# LGT-92_v1_5.net
KiCad netlist of a schematic drawn in EAGLE
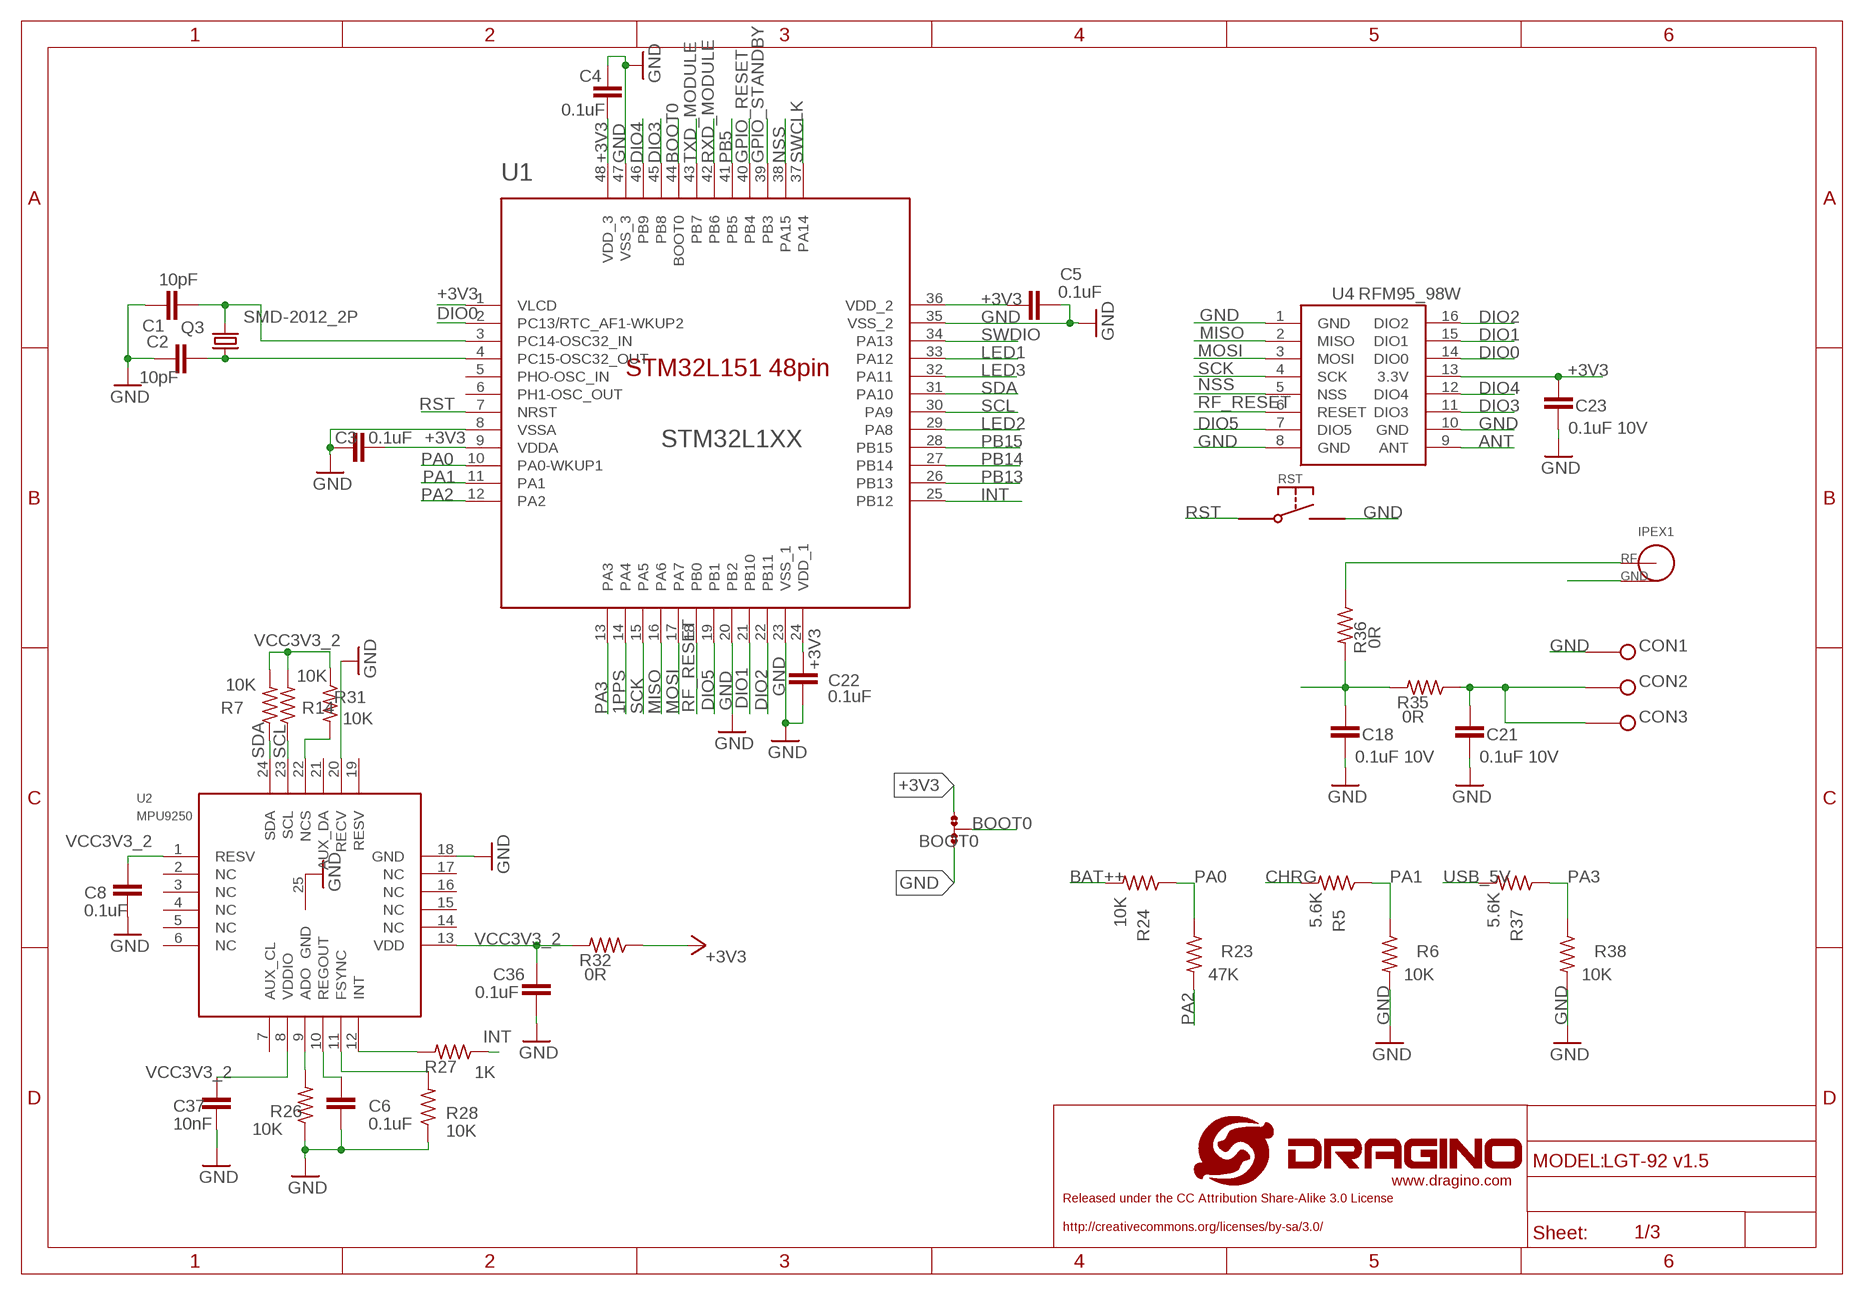
[diagram p0: schematic, sheet 1]
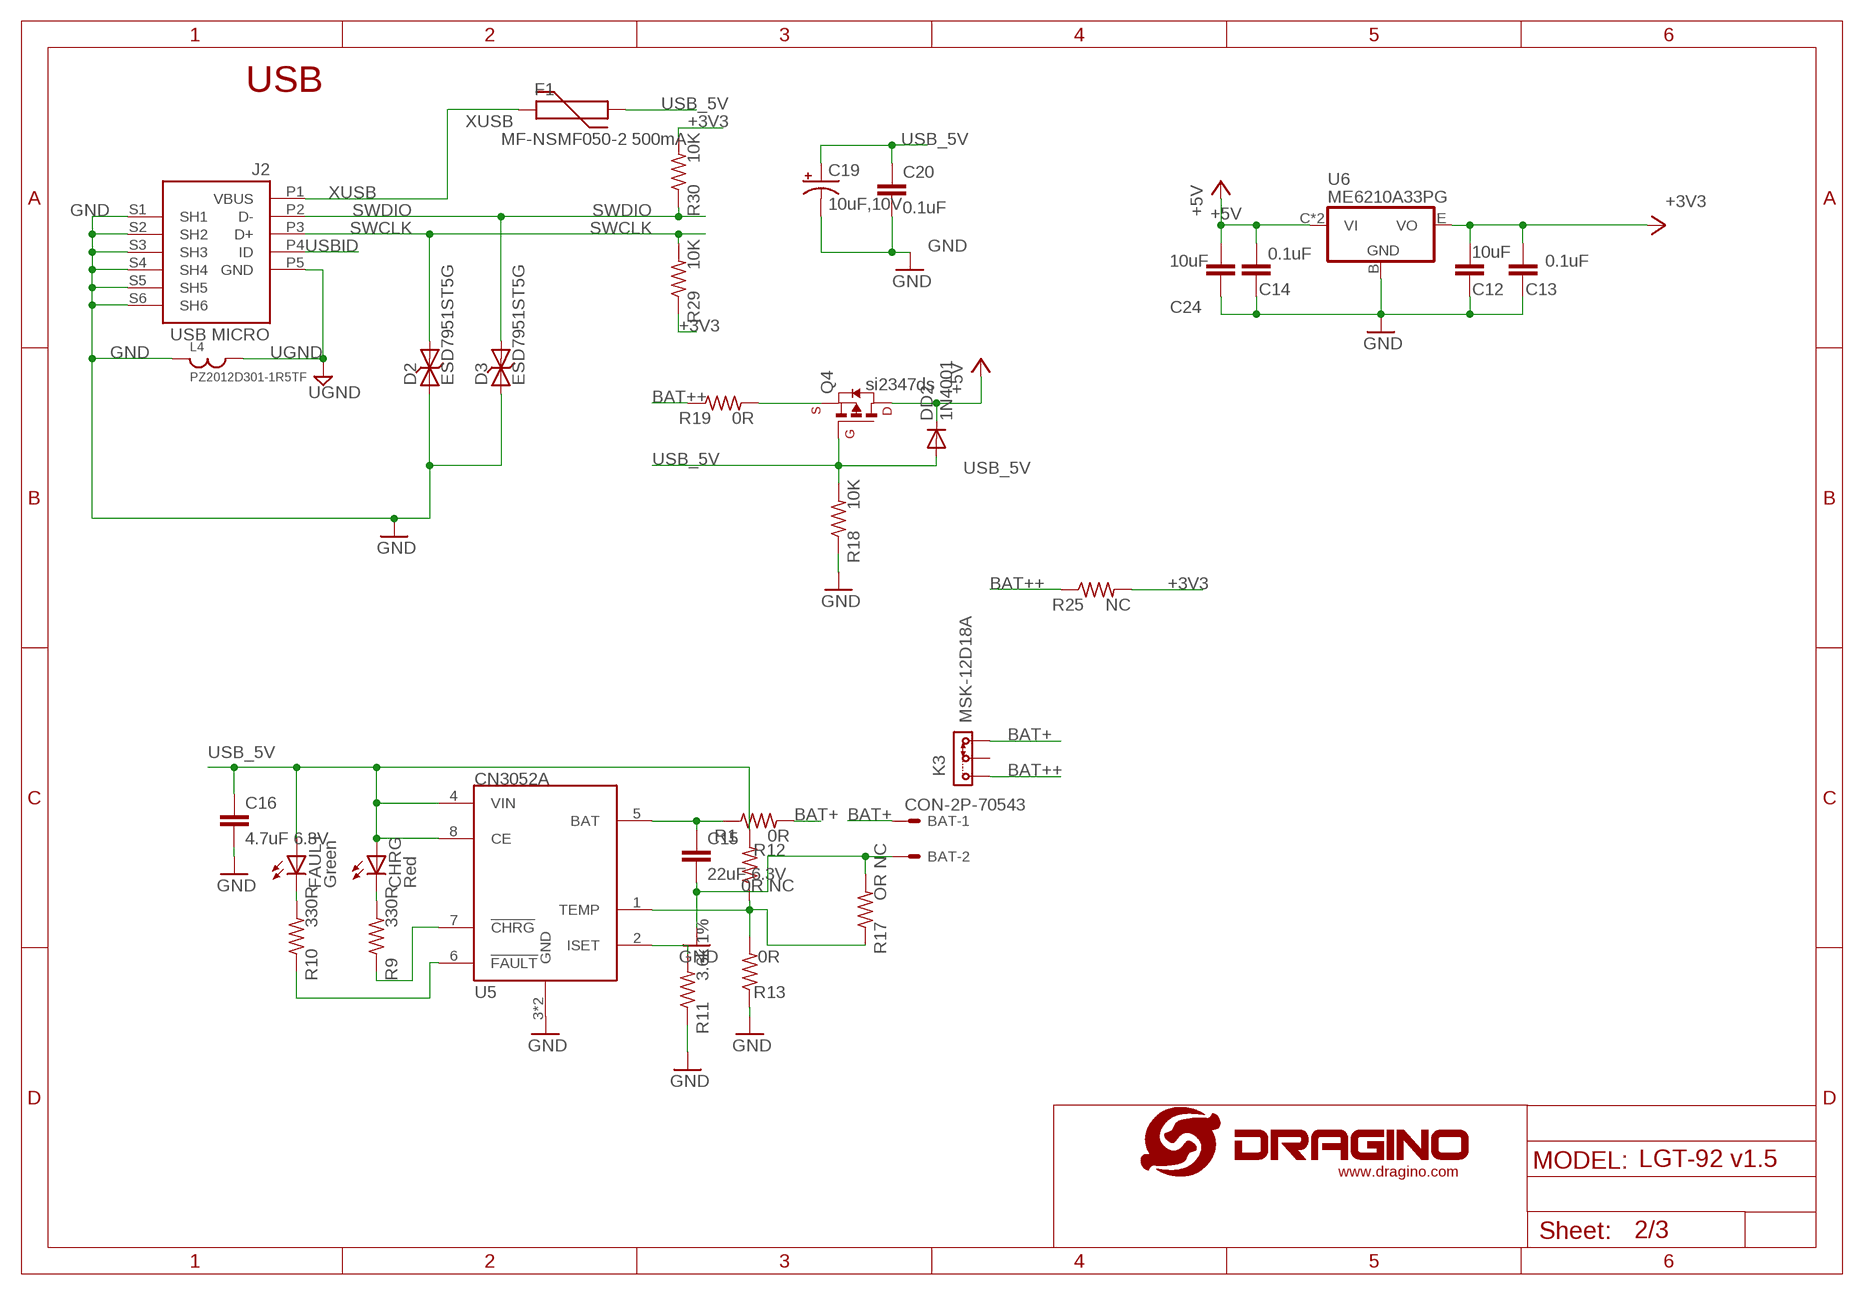
[diagram p1: schematic, sheet 2]
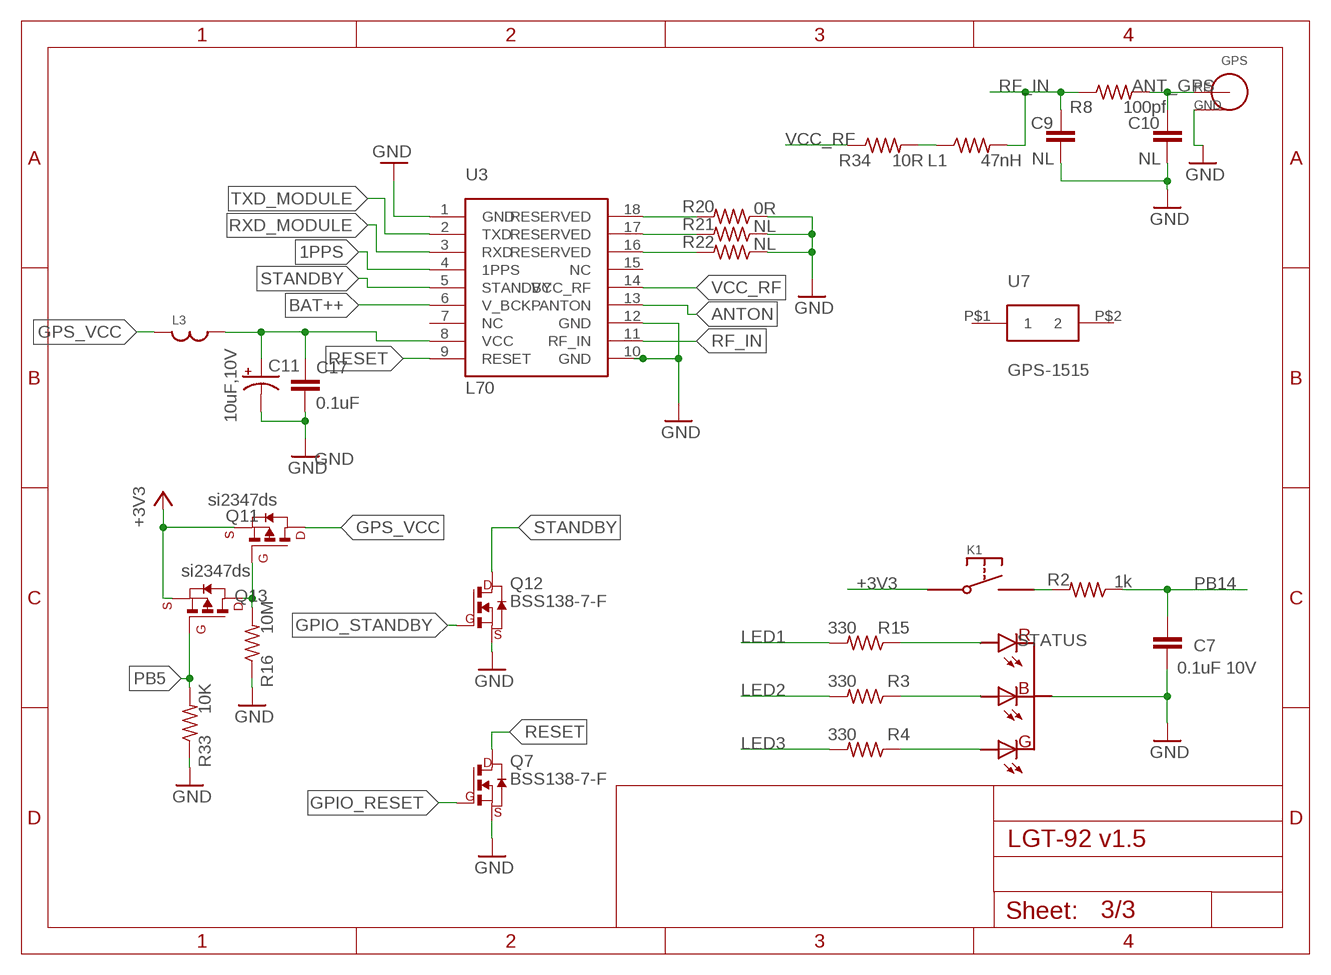
[diagram p2: schematic, sheet 3]

(export (version "E")
  (design (tool "Eeschema 10.0.6"))
  (components
    (comp (ref "BAT")
      (value "CON-2P-70543")
      (footprint "eagle-import:70543-02")
      (libsource (lib "eagle-import") (part "CON-2P-70543"))
    )
    (comp (ref "C12")
      (value "10uF")
      (footprint "eagle-import:C0805")
      (libsource (lib "eagle-import") (part "C-EUC0805"))
    )
    (comp (ref "C13")
      (value "0.1uF")
      (footprint "eagle-import:C0402")
      (libsource (lib "eagle-import") (part "C-EUC0402"))
    )
    (comp (ref "C14")
      (value "0.1uF")
      (footprint "eagle-import:C0402")
      (libsource (lib "eagle-import") (part "C-EUC0402"))
    )
    (comp (ref "C15")
      (value "22uF 6.3V")
      (footprint "eagle-import:C0603")
      (libsource (lib "eagle-import") (part "C-EUC0603"))
    )
    (comp (ref "C16")
      (value "4.7uF 6.3V")
      (footprint "eagle-import:C0603")
      (libsource (lib "eagle-import") (part "C-EUC0603"))
    )
    (comp (ref "C19")
      (value "10uF,10V")
      (footprint "eagle-import:SMC_A")
      (libsource (lib "eagle-import") (part "CPOL-USSMCA"))
    )
    (comp (ref "C20")
      (value "0.1uF")
      (footprint "eagle-import:C0402")
      (libsource (lib "eagle-import") (part "dragino-passive_C-EUC0402"))
    )
    (comp (ref "C24")
      (value "10uF")
      (footprint "eagle-import:C0805")
      (libsource (lib "eagle-import") (part "C-EUC0805"))
    )
    (comp (ref "CHRG")
      (value "Red")
      (footprint "eagle-import:DRAGINO_CHIPLED_0603")
      (libsource (lib "eagle-import") (part "DRAGINO_LEDCHIPLED_0603"))
    )
    (comp (ref "D2")
      (value "ESD7951ST5G")
      (footprint "eagle-import:SOD_923")
      (libsource (lib "eagle-import") (part "TVSSOD?923"))
    )
    (comp (ref "D3")
      (value "ESD7951ST5G")
      (footprint "eagle-import:SOD_923")
      (libsource (lib "eagle-import") (part "TVSSOD?923"))
    )
    (comp (ref "DD2")
      (value "1N4001")
      (footprint "eagle-import:DIODE_DO214AC")
      (libsource (lib "eagle-import") (part "DIODEDO214AC"))
    )
    (comp (ref "F1")
      (value "MF-NSMF050-2 500mA")
      (footprint "eagle-import:R1206$1")
      (libsource (lib "eagle-import") (part "FUSE1206"))
    )
    (comp (ref "FAULT")
      (value "Green")
      (footprint "eagle-import:DRAGINO_CHIPLED_0603")
      (libsource (lib "eagle-import") (part "DRAGINO_LEDCHIPLED_0603"))
    )
    (comp (ref "J2")
      (value "USB MICRO")
      (footprint "eagle-import:CON2_USB_MICRO_B_AT")
      (libsource (lib "eagle-import") (part "MYCON2_USB-MINI-B"))
    )
    (comp (ref "K3")
      (value "MSK-12D18A")
      (footprint "eagle-import:MSK-12D18A")
      (libsource (lib "eagle-import") (part "MSK-12D18A"))
    )
    (comp (ref "L4")
      (value "PZ2012D301-1R5TF")
      (footprint "eagle-import:C0805")
      (libsource (lib "eagle-import") (part "BEADS0805"))
    )
    (comp (ref "Q4")
      (value "si2347ds")
      (footprint "eagle-import:SOT-23-HIGH-POWER")
      (libsource (lib "eagle-import") (part "P-MOSFET_HP"))
    )
    (comp (ref "R1")
      (value "0R")
      (footprint "eagle-import:R0805")
      (libsource (lib "eagle-import") (part "R-US_R0805"))
    )
    (comp (ref "R9")
      (value "330R")
      (footprint "eagle-import:R0402")
      (libsource (lib "eagle-import") (part "R-US_R0402"))
    )
    (comp (ref "R10")
      (value "330R")
      (footprint "eagle-import:R0402")
      (libsource (lib "eagle-import") (part "R-US_R0402"))
    )
    (comp (ref "R11")
      (value "3.6k 1%")
      (footprint "eagle-import:R0402")
      (libsource (lib "eagle-import") (part "R-US_R0402"))
    )
    (comp (ref "R12")
      (value "0R NC")
      (footprint "eagle-import:R0402")
      (libsource (lib "eagle-import") (part "R-US_R0402"))
    )
    (comp (ref "R13")
      (value "0R")
      (footprint "eagle-import:R0402")
      (libsource (lib "eagle-import") (part "R-US_R0402"))
    )
    (comp (ref "R17")
      (value "OR NC")
      (footprint "eagle-import:R0402")
      (libsource (lib "eagle-import") (part "R-US_R0402"))
    )
    (comp (ref "R18")
      (value "10K")
      (footprint "eagle-import:R0402")
      (libsource (lib "eagle-import") (part "R-US_R0402"))
    )
    (comp (ref "R19")
      (value "0R")
      (footprint "eagle-import:R0805")
      (libsource (lib "eagle-import") (part "R-US_R0805"))
    )
    (comp (ref "R25")
      (value "NC")
      (footprint "eagle-import:R0805")
      (libsource (lib "eagle-import") (part "R-US_R0805"))
    )
    (comp (ref "R29")
      (value "10K")
      (footprint "eagle-import:R0402")
      (libsource (lib "eagle-import") (part "R-US_R0402"))
    )
    (comp (ref "R30")
      (value "10K")
      (footprint "eagle-import:R0402")
      (libsource (lib "eagle-import") (part "R-US_R0402"))
    )
    (comp (ref "U5")
      (value "CN3052A")
      (footprint "eagle-import:CN3052A")
      (libsource (lib "eagle-import") (part "CN3052A"))
    )
    (comp (ref "U6")
      (value "ME6210A33PG")
      (footprint "eagle-import:SOT-89")
      (libsource (lib "eagle-import") (part "ME6210A33PG"))
    )
    (comp (ref "C7")
      (value "0.1uF 10V")
      (footprint "eagle-import:C0402")
      (libsource (lib "eagle-import") (part "dragino-passive_C-EUC0402"))
    )
    (comp (ref "C9")
      (value "NL")
      (footprint "eagle-import:C0402")
      (libsource (lib "eagle-import") (part "dragino-passive_C-EUC0402"))
    )
    (comp (ref "C10")
      (value "NL")
      (footprint "eagle-import:C0402")
      (libsource (lib "eagle-import") (part "dragino-passive_C-EUC0402"))
    )
    (comp (ref "C11")
      (value "10uF,10V")
      (footprint "eagle-import:SMC_A")
      (libsource (lib "eagle-import") (part "CPOL-USSMCA"))
    )
    (comp (ref "C17")
      (value "0.1uF")
      (footprint "eagle-import:C0402")
      (libsource (lib "eagle-import") (part "dragino-passive_C-EUC0402"))
    )
    (comp (ref "GPS")
      (value "I-PEX,NL")
      (footprint "eagle-import:I-PEX")
      (libsource (lib "eagle-import") (part "I-PEX"))
    )
    (comp (ref "K1")
      (value "S-LAY")
      (footprint "eagle-import:KEY")
      (libsource (lib "eagle-import") (part "S-LAY"))
    )
    (comp (ref "L1")
      (value "47nH")
      (footprint "eagle-import:R0402")
      (libsource (lib "eagle-import") (part "R-US_R0402"))
    )
    (comp (ref "L3")
      (value "JLC-PZ2012D800-3R0TF")
      (footprint "eagle-import:C0805")
      (libsource (lib "eagle-import") (part "BEADS0805"))
    )
    (comp (ref "Q7")
      (value "BSS138-7-F")
      (footprint "eagle-import:SOT-23")
      (libsource (lib "eagle-import") (part "NMOSFET"))
    )
    (comp (ref "Q11")
      (value "si2347ds")
      (footprint "eagle-import:SOT-23-HIGH-POWER")
      (libsource (lib "eagle-import") (part "P-MOSFET_HP"))
    )
    (comp (ref "Q12")
      (value "BSS138-7-F")
      (footprint "eagle-import:SOT-23")
      (libsource (lib "eagle-import") (part "NMOSFET"))
    )
    (comp (ref "Q13")
      (value "si2347ds")
      (footprint "eagle-import:SOT-23-HIGH-POWER")
      (libsource (lib "eagle-import") (part "P-MOSFET_HP"))
    )
    (comp (ref "R2")
      (value "1k")
      (footprint "eagle-import:R0402")
      (libsource (lib "eagle-import") (part "R-US_R0402"))
    )
    (comp (ref "R3")
      (value "330")
      (footprint "eagle-import:R0402")
      (libsource (lib "eagle-import") (part "R-US_R0402"))
    )
    (comp (ref "R4")
      (value "330")
      (footprint "eagle-import:R0402")
      (libsource (lib "eagle-import") (part "R-US_R0402"))
    )
    (comp (ref "R8")
      (value "100pf")
      (footprint "eagle-import:R0402")
      (libsource (lib "eagle-import") (part "R-US_R0402"))
    )
    (comp (ref "R15")
      (value "330")
      (footprint "eagle-import:R0402")
      (libsource (lib "eagle-import") (part "R-US_R0402"))
    )
    (comp (ref "R16")
      (value "10M")
      (footprint "eagle-import:R0402")
      (libsource (lib "eagle-import") (part "R-US_R0402"))
    )
    (comp (ref "R20")
      (value "0R")
      (footprint "eagle-import:R0402")
      (libsource (lib "eagle-import") (part "R-US_R0402"))
    )
    (comp (ref "R21")
      (value "NL")
      (footprint "eagle-import:R0402")
      (libsource (lib "eagle-import") (part "R-US_R0402"))
    )
    (comp (ref "R22")
      (value "NL")
      (footprint "eagle-import:R0402")
      (libsource (lib "eagle-import") (part "R-US_R0402"))
    )
    (comp (ref "R33")
      (value "10K")
      (footprint "eagle-import:R0402")
      (libsource (lib "eagle-import") (part "R-US_R0402"))
    )
    (comp (ref "R34")
      (value "10R")
      (footprint "eagle-import:R0402")
      (libsource (lib "eagle-import") (part "R-US_R0402"))
    )
    (comp (ref "STATUS")
      (value "LED-RGB-THR-5MM-GNDSMD-3528")
      (footprint "eagle-import:LED-3528")
      (libsource (lib "eagle-import") (part "LED-RGB-THR-5MM-GNDSMD-3528"))
    )
    (comp (ref "U3")
      (value "L70")
      (footprint "eagle-import:L70")
      (libsource (lib "eagle-import") (part "L70"))
    )
    (comp (ref "U7")
      (value "GPS-1515")
      (footprint "eagle-import:GPS-YY")
      (libsource (lib "eagle-import") (part "GPS-1515"))
    )
    (comp (ref "BOOT0")
      (value "0R-JUMPA0R-JMP-0402")
      (footprint "eagle-import:A0R-JMP-0402")
      (libsource (lib "eagle-import") (part "0R-JUMPA0R-JMP-0402"))
    )
    (comp (ref "C1")
      (value "10pF")
      (footprint "eagle-import:C0402")
      (libsource (lib "eagle-import") (part "dragino-passive_C-EUC0402"))
    )
    (comp (ref "C2")
      (value "10pF")
      (footprint "eagle-import:C0402")
      (libsource (lib "eagle-import") (part "dragino-passive_C-EUC0402"))
    )
    (comp (ref "C3")
      (value "0.1uF")
      (footprint "eagle-import:C0402")
      (libsource (lib "eagle-import") (part "dragino-passive_C-EUC0402"))
    )
    (comp (ref "C4")
      (value "0.1uF")
      (footprint "eagle-import:C0402")
      (libsource (lib "eagle-import") (part "dragino-passive_C-EUC0402"))
    )
    (comp (ref "C5")
      (value "0.1uF")
      (footprint "eagle-import:C0402")
      (libsource (lib "eagle-import") (part "dragino-passive_C-EUC0402"))
    )
    (comp (ref "C6")
      (value "0.1uF")
      (footprint "eagle-import:C0402")
      (libsource (lib "eagle-import") (part "C-EUC0402"))
    )
    (comp (ref "C8")
      (value "0.1uF")
      (footprint "eagle-import:C0402")
      (libsource (lib "eagle-import") (part "C-EUC0402"))
    )
    (comp (ref "C18")
      (value "0.1uF 10V")
      (footprint "eagle-import:C0402")
      (libsource (lib "eagle-import") (part "dragino-passive_C-EUC0402"))
    )
    (comp (ref "C21")
      (value "0.1uF 10V")
      (footprint "eagle-import:C0402")
      (libsource (lib "eagle-import") (part "dragino-passive_C-EUC0402"))
    )
    (comp (ref "C22")
      (value "0.1uF")
      (footprint "eagle-import:C0402")
      (libsource (lib "eagle-import") (part "dragino-passive_C-EUC0402"))
    )
    (comp (ref "C23")
      (value "0.1uF 10V")
      (footprint "eagle-import:C0402")
      (libsource (lib "eagle-import") (part "dragino-passive_C-EUC0402"))
    )
    (comp (ref "C36")
      (value "0.1uF")
      (footprint "eagle-import:C0402")
      (libsource (lib "eagle-import") (part "C-EUC0402"))
    )
    (comp (ref "C37")
      (value "10nF")
      (footprint "eagle-import:C0402")
      (libsource (lib "eagle-import") (part "C-EUC0402"))
    )
    (comp (ref "CON1")
      (value "POGOPINSMT-2.0")
      (footprint "eagle-import:POGOPIN-SMT-2.0")
      (libsource (lib "eagle-import") (part "POGOPINSMT-2.0"))
    )
    (comp (ref "CON2")
      (value "POGOPINSMT-2.0")
      (footprint "eagle-import:POGOPIN-SMT-2.0")
      (libsource (lib "eagle-import") (part "POGOPINSMT-2.0"))
    )
    (comp (ref "CON3")
      (value "POGOPINSMT-2.0")
      (footprint "eagle-import:POGOPIN-SMT-2.0")
      (libsource (lib "eagle-import") (part "POGOPINSMT-2.0"))
    )
    (comp (ref "IPEX1")
      (value "I-PEX")
      (footprint "eagle-import:I-PEX")
      (libsource (lib "eagle-import") (part "I-PEX"))
    )
    (comp (ref "Q3")
      (value "SMD-2012_2P")
      (footprint "eagle-import:32.768K")
      (libsource (lib "eagle-import") (part "SMD-2012_2P"))
    )
    (comp (ref "R5")
      (value "5.6K")
      (footprint "eagle-import:R0402")
      (libsource (lib "eagle-import") (part "R-US_R0402"))
    )
    (comp (ref "R6")
      (value "10K")
      (footprint "eagle-import:R0402")
      (libsource (lib "eagle-import") (part "R-US_R0402"))
    )
    (comp (ref "R7")
      (value "10K")
      (footprint "eagle-import:R0402")
      (libsource (lib "eagle-import") (part "R-US_R0402"))
    )
    (comp (ref "R14")
      (value "10K")
      (footprint "eagle-import:R0402")
      (libsource (lib "eagle-import") (part "R-US_R0402"))
    )
    (comp (ref "R23")
      (value "47K")
      (footprint "eagle-import:R0402")
      (libsource (lib "eagle-import") (part "R-US_R0402"))
    )
    (comp (ref "R24")
      (value "10K")
      (footprint "eagle-import:R0402")
      (libsource (lib "eagle-import") (part "R-US_R0402"))
    )
    (comp (ref "R26")
      (value "10K")
      (footprint "eagle-import:R0402")
      (libsource (lib "eagle-import") (part "R-US_R0402"))
    )
    (comp (ref "R27")
      (value "1K")
      (footprint "eagle-import:R0402")
      (libsource (lib "eagle-import") (part "R-US_R0402"))
    )
    (comp (ref "R28")
      (value "10K")
      (footprint "eagle-import:R0402")
      (libsource (lib "eagle-import") (part "R-US_R0402"))
    )
    (comp (ref "R31")
      (value "10K")
      (footprint "eagle-import:R0402")
      (libsource (lib "eagle-import") (part "R-US_R0402"))
    )
    (comp (ref "R32")
      (value "0R")
      (footprint "eagle-import:R0402")
      (libsource (lib "eagle-import") (part "R-US_R0402"))
    )
    (comp (ref "R35")
      (value "0R")
      (footprint "eagle-import:R0402")
      (libsource (lib "eagle-import") (part "R-US_R0402"))
    )
    (comp (ref "R36")
      (value "0R")
      (footprint "eagle-import:R0402")
      (libsource (lib "eagle-import") (part "R-US_R0402"))
    )
    (comp (ref "R37")
      (value "5.6K")
      (footprint "eagle-import:R0402")
      (libsource (lib "eagle-import") (part "R-US_R0402"))
    )
    (comp (ref "R38")
      (value "10K")
      (footprint "eagle-import:R0402")
      (libsource (lib "eagle-import") (part "R-US_R0402"))
    )
    (comp (ref "RST")
      (value "SWITCHTS-017")
      (footprint "eagle-import:TS-017")
      (libsource (lib "eagle-import") (part "SWITCHTS-017"))
    )
    (comp (ref "U1")
      (value "STM32L1XX")
      (footprint "eagle-import:STM32L1XX")
      (libsource (lib "eagle-import") (part "STM32L1XX"))
    )
    (comp (ref "U2")
      (value "MPU9250")
      (footprint "eagle-import:QFN-24")
      (libsource (lib "eagle-import") (part "MPU9250"))
    )
    (comp (ref "U4")
      (value "RFM95_98W")
      (footprint "eagle-import:RFM95_98W")
      (libsource (lib "eagle-import") (part "RFM95_98W"))
    )
  )
  (nets
    (net (code "1") (name "+3V3") (class "Default")
      (node (ref "BOOT0") (pin "1") (pinfunction "1_1") (pintype "passive"))
      (node (ref "C12") (pin "2") (pinfunction "2_2") (pintype "passive"))
      (node (ref "C13") (pin "2") (pinfunction "2_2") (pintype "passive"))
      (node (ref "C22") (pin "2") (pinfunction "2_2") (pintype "passive"))
      (node (ref "C23") (pin "2") (pinfunction "2_2") (pintype "passive"))
      (node (ref "C3") (pin "1") (pinfunction "1_1") (pintype "passive"))
      (node (ref "C4") (pin "1") (pinfunction "1_1") (pintype "passive"))
      (node (ref "C5") (pin "2") (pinfunction "2_2") (pintype "passive"))
      (node (ref "K1") (pin "1") (pinfunction "P$1_1") (pintype "bidirectional"))
      (node (ref "K1") (pin "2") (pinfunction "P$1_2") (pintype "bidirectional"))
      (node (ref "K1") (pin "5") (pinfunction "P$1_5") (pintype "bidirectional"))
      (node (ref "Q11") (pin "2") (pinfunction "S_2") (pintype "passive"))
      (node (ref "Q13") (pin "2") (pinfunction "S_2") (pintype "passive"))
      (node (ref "R25") (pin "2") (pinfunction "2_2") (pintype "passive"))
      (node (ref "R29") (pin "1") (pinfunction "1_1") (pintype "passive"))
      (node (ref "R30") (pin "2") (pinfunction "2_2") (pintype "passive"))
      (node (ref "R32") (pin "1") (pinfunction "1_1") (pintype "passive"))
      (node (ref "U1") (pin "1") (pinfunction "VLCD_1") (pintype "bidirectional"))
      (node (ref "U1") (pin "24") (pinfunction "VDD_1_24") (pintype "bidirectional"))
      (node (ref "U1") (pin "36") (pinfunction "VDD_2_36") (pintype "bidirectional"))
      (node (ref "U1") (pin "48") (pinfunction "VDD_3_48") (pintype "bidirectional"))
      (node (ref "U1") (pin "9") (pinfunction "VDDA_9") (pintype "bidirectional"))
      (node (ref "U4") (pin "13") (pinfunction "3.3V_13") (pintype "power_in"))
      (node (ref "U6") (pin "E") (pinfunction "VO_E") (pintype "passive"))
    )
    (net (code "2") (name "+5V") (class "Default")
      (node (ref "C14") (pin "2") (pinfunction "2_2") (pintype "passive"))
      (node (ref "C24") (pin "2") (pinfunction "2_2") (pintype "passive"))
      (node (ref "DD2") (pin "C") (pinfunction "C_C") (pintype "passive"))
      (node (ref "Q4") (pin "1") (pinfunction "D_1") (pintype "passive"))
      (node (ref "U6") (pin "C") (pinfunction "VI_C") (pintype "input"))
      (node (ref "U6") (pin "C@1") (pinfunction "VI_C@1") (pintype "input"))
    )
    (net (code "3") (name "1PPS") (class "Default")
      (node (ref "U1") (pin "14") (pinfunction "PA4_14") (pintype "bidirectional"))
      (node (ref "U3") (pin "4") (pinfunction "1PPS_4") (pintype "bidirectional"))
    )
    (net (code "4") (name "ANT") (class "Default")
      (node (ref "C18") (pin "2") (pinfunction "2_2") (pintype "passive"))
      (node (ref "R35") (pin "2") (pinfunction "2_2") (pintype "passive"))
      (node (ref "R36") (pin "2") (pinfunction "2_2") (pintype "passive"))
      (node (ref "U4") (pin "9") (pinfunction "ANT_9") (pintype "bidirectional"))
    )
    (net (code "5") (name "ANTON") (class "Default")
      (node (ref "U3") (pin "13") (pinfunction "ANTON_13") (pintype "bidirectional"))
    )
    (net (code "6") (name "ANT_GPS") (class "Default")
      (node (ref "C10") (pin "1") (pinfunction "1_1") (pintype "passive"))
      (node (ref "GPS") (pin "SIG") (pinfunction "SIG_SIG") (pintype "passive"))
      (node (ref "R8") (pin "2") (pinfunction "2_2") (pintype "passive"))
    )
    (net (code "7") (name "BAT+") (class "Default")
      (node (ref "BAT") (pin "1") (pinfunction "S_1") (pintype "passive"))
      (node (ref "K3") (pin "3") (pinfunction "3_3") (pintype "passive"))
      (node (ref "R1") (pin "2") (pinfunction "2_2") (pintype "passive"))
    )
    (net (code "8") (name "BAT++") (class "Default")
      (node (ref "K3") (pin "1") (pinfunction "1_1") (pintype "passive"))
      (node (ref "R19") (pin "1") (pinfunction "1_1") (pintype "passive"))
      (node (ref "R24") (pin "2") (pinfunction "2_2") (pintype "passive"))
      (node (ref "R25") (pin "1") (pinfunction "1_1") (pintype "passive"))
      (node (ref "U3") (pin "6") (pinfunction "V_BCKP_6") (pintype "bidirectional"))
    )
    (net (code "9") (name "BOOT0") (class "Default")
      (node (ref "BOOT0") (pin "2") (pinfunction "2_2") (pintype "passive"))
      (node (ref "U1") (pin "44") (pinfunction "BOOT0_44") (pintype "bidirectional"))
    )
    (net (code "10") (name "CHRG") (class "Default")
      (node (ref "R5") (pin "2") (pinfunction "2_2") (pintype "passive"))
      (node (ref "R9") (pin "1") (pinfunction "1_1") (pintype "passive"))
      (node (ref "U5") (pin "7") (pinfunction "~{CHRG}_7") (pintype "bidirectional"))
    )
    (net (code "11") (name "DIO0") (class "Default")
      (node (ref "U1") (pin "2") (pinfunction "PC13/RTC_AF1-WKUP2_2") (pintype "bidirectional"))
      (node (ref "U4") (pin "14") (pinfunction "DIO0_14") (pintype "bidirectional"))
    )
    (net (code "12") (name "DIO1") (class "Default")
      (node (ref "U1") (pin "21") (pinfunction "PB10_21") (pintype "bidirectional"))
      (node (ref "U4") (pin "15") (pinfunction "DIO1_15") (pintype "bidirectional"))
    )
    (net (code "13") (name "DIO2") (class "Default")
      (node (ref "U1") (pin "22") (pinfunction "PB11_22") (pintype "bidirectional"))
      (node (ref "U4") (pin "16") (pinfunction "DIO2_16") (pintype "bidirectional"))
    )
    (net (code "14") (name "DIO3") (class "Default")
      (node (ref "U1") (pin "45") (pinfunction "PB8_45") (pintype "bidirectional"))
      (node (ref "U4") (pin "11") (pinfunction "DIO3_11") (pintype "bidirectional"))
    )
    (net (code "15") (name "DIO4") (class "Default")
      (node (ref "U1") (pin "46") (pinfunction "PB9_46") (pintype "bidirectional"))
      (node (ref "U4") (pin "12") (pinfunction "DIO4_12") (pintype "bidirectional"))
    )
    (net (code "16") (name "DIO5") (class "Default")
      (node (ref "U1") (pin "19") (pinfunction "PB1_19") (pintype "bidirectional"))
      (node (ref "U4") (pin "7") (pinfunction "DIO5_7") (pintype "bidirectional"))
    )
    (net (code "17") (name "GND") (class "Default")
      (node (ref "BAT") (pin "2") (pinfunction "2_2") (pintype "passive"))
      (node (ref "BOOT0") (pin "3") (pinfunction "3_3") (pintype "passive"))
      (node (ref "C1") (pin "1") (pinfunction "1_1") (pintype "passive"))
      (node (ref "C10") (pin "2") (pinfunction "2_2") (pintype "passive"))
      (node (ref "C11") (pin "-") (pinfunction "-_-") (pintype "passive"))
      (node (ref "C12") (pin "1") (pinfunction "1_1") (pintype "passive"))
      (node (ref "C13") (pin "1") (pinfunction "1_1") (pintype "passive"))
      (node (ref "C14") (pin "1") (pinfunction "1_1") (pintype "passive"))
      (node (ref "C15") (pin "2") (pinfunction "2_2") (pintype "passive"))
      (node (ref "C16") (pin "2") (pinfunction "2_2") (pintype "passive"))
      (node (ref "C17") (pin "2") (pinfunction "2_2") (pintype "passive"))
      (node (ref "C18") (pin "1") (pinfunction "1_1") (pintype "passive"))
      (node (ref "C19") (pin "-") (pinfunction "-_-") (pintype "passive"))
      (node (ref "C2") (pin "1") (pinfunction "1_1") (pintype "passive"))
      (node (ref "C20") (pin "2") (pinfunction "2_2") (pintype "passive"))
      (node (ref "C21") (pin "1") (pinfunction "1_1") (pintype "passive"))
      (node (ref "C22") (pin "1") (pinfunction "1_1") (pintype "passive"))
      (node (ref "C23") (pin "1") (pinfunction "1_1") (pintype "passive"))
      (node (ref "C24") (pin "1") (pinfunction "1_1") (pintype "passive"))
      (node (ref "C3") (pin "2") (pinfunction "2_2") (pintype "passive"))
      (node (ref "C36") (pin "1") (pinfunction "1_1") (pintype "passive"))
      (node (ref "C37") (pin "1") (pinfunction "1_1") (pintype "passive"))
      (node (ref "C4") (pin "2") (pinfunction "2_2") (pintype "passive"))
      (node (ref "C5") (pin "1") (pinfunction "1_1") (pintype "passive"))
      (node (ref "C6") (pin "1") (pinfunction "1_1") (pintype "passive"))
      (node (ref "C7") (pin "1") (pinfunction "1_1") (pintype "passive"))
      (node (ref "C8") (pin "1") (pinfunction "1_1") (pintype "passive"))
      (node (ref "C9") (pin "2") (pinfunction "2_2") (pintype "passive"))
      (node (ref "CON1") (pin "1") (pinfunction "TP_1") (pintype "bidirectional"))
      (node (ref "D2") (pin "P$1") (pinfunction "1_P$1") (pintype "passive"))
      (node (ref "D3") (pin "P$1") (pinfunction "1_P$1") (pintype "passive"))
      (node (ref "GPS") (pin "GND") (pinfunction "GND_GND") (pintype "passive"))
      (node (ref "GPS") (pin "GND1") (pinfunction "GND_GND1") (pintype "passive"))
      (node (ref "IPEX1") (pin "GND") (pinfunction "GND_GND") (pintype "passive"))
      (node (ref "IPEX1") (pin "GND1") (pinfunction "GND_GND1") (pintype "passive"))
      (node (ref "J2") (pin "S1") (pinfunction "SH1_S1") (pintype "passive"))
      (node (ref "J2") (pin "S2") (pinfunction "SH2_S2") (pintype "passive"))
      (node (ref "J2") (pin "S3") (pinfunction "SH3_S3") (pintype "passive"))
      (node (ref "J2") (pin "S4") (pinfunction "SH4_S4") (pintype "passive"))
      (node (ref "J2") (pin "S5") (pinfunction "SH5_S5") (pintype "passive"))
      (node (ref "J2") (pin "S6") (pinfunction "SH6_S6") (pintype "passive"))
      (node (ref "L4") (pin "1") (pinfunction "P$1_1") (pintype "bidirectional"))
      (node (ref "Q12") (pin "2") (pinfunction "S_2") (pintype "passive"))
      (node (ref "Q7") (pin "2") (pinfunction "S_2") (pintype "passive"))
      (node (ref "R11") (pin "1") (pinfunction "1_1") (pintype "passive"))
      (node (ref "R13") (pin "1") (pinfunction "1_1") (pintype "passive"))
      (node (ref "R16") (pin "1") (pinfunction "1_1") (pintype "passive"))
      (node (ref "R17") (pin "2") (pinfunction "2_2") (pintype "passive"))
      (node (ref "R18") (pin "1") (pinfunction "1_1") (pintype "passive"))
      (node (ref "R20") (pin "1") (pinfunction "1_1") (pintype "passive"))
      (node (ref "R21") (pin "1") (pinfunction "1_1") (pintype "passive"))
      (node (ref "R22") (pin "1") (pinfunction "1_1") (pintype "passive"))
      (node (ref "R26") (pin "1") (pinfunction "1_1") (pintype "passive"))
      (node (ref "R28") (pin "1") (pinfunction "1_1") (pintype "passive"))
      (node (ref "R33") (pin "1") (pinfunction "1_1") (pintype "passive"))
      (node (ref "R38") (pin "2") (pinfunction "2_2") (pintype "passive"))
      (node (ref "R6") (pin "2") (pinfunction "2_2") (pintype "passive"))
      (node (ref "RST") (pin "P$2") (pinfunction "P$2_P$2") (pintype "bidirectional"))
      (node (ref "STATUS") (pin "+") (pinfunction "C_+") (pintype "passive"))
      (node (ref "U1") (pin "20") (pinfunction "PB2_20") (pintype "bidirectional"))
      (node (ref "U1") (pin "23") (pinfunction "VSS_1_23") (pintype "bidirectional"))
      (node (ref "U1") (pin "35") (pinfunction "VSS_2_35") (pintype "bidirectional"))
      (node (ref "U1") (pin "47") (pinfunction "VSS_3_47") (pintype "bidirectional"))
      (node (ref "U1") (pin "8") (pinfunction "VSSA_8") (pintype "bidirectional"))
      (node (ref "U2") (pin "18") (pinfunction "GND_18") (pintype "bidirectional"))
      (node (ref "U2") (pin "20") (pinfunction "RECV_20") (pintype "bidirectional"))
      (node (ref "U2") (pin "25") (pinfunction "GND_25") (pintype "bidirectional"))
      (node (ref "U3") (pin "1") (pinfunction "GND_1") (pintype "bidirectional"))
      (node (ref "U3") (pin "10") (pinfunction "GND_10") (pintype "bidirectional"))
      (node (ref "U3") (pin "12") (pinfunction "GND_12") (pintype "bidirectional"))
      (node (ref "U4") (pin "1") (pinfunction "GND_1") (pintype "power_in"))
      (node (ref "U4") (pin "10") (pinfunction "GND_10") (pintype "power_in"))
      (node (ref "U4") (pin "8") (pinfunction "GND_8") (pintype "power_in"))
      (node (ref "U5") (pin "3") (pinfunction "GND_3") (pintype "bidirectional"))
      (node (ref "U5") (pin "P$1") (pinfunction "GND_P$1") (pintype "bidirectional"))
      (node (ref "U6") (pin "B") (pinfunction "GND_B") (pintype "passive"))
    )
    (net (code "18") (name "GPIO_RESET") (class "Default")
      (node (ref "Q7") (pin "3") (pinfunction "G_3") (pintype "passive"))
      (node (ref "U1") (pin "40") (pinfunction "PB4_40") (pintype "bidirectional"))
    )
    (net (code "19") (name "GPIO_STANDBY") (class "Default")
      (node (ref "Q12") (pin "3") (pinfunction "G_3") (pintype "passive"))
      (node (ref "U1") (pin "39") (pinfunction "PB3_39") (pintype "bidirectional"))
    )
    (net (code "20") (name "GPS_VCC") (class "Default")
      (node (ref "L3") (pin "1") (pinfunction "P$1_1") (pintype "bidirectional"))
      (node (ref "Q11") (pin "1") (pinfunction "D_1") (pintype "passive"))
    )
    (net (code "21") (name "INT") (class "Default")
      (node (ref "R27") (pin "1") (pinfunction "1_1") (pintype "passive"))
      (node (ref "U1") (pin "25") (pinfunction "PB12_25") (pintype "bidirectional"))
    )
    (net (code "22") (name "LED1") (class "Default")
      (node (ref "R15") (pin "2") (pinfunction "2_2") (pintype "passive"))
      (node (ref "U1") (pin "33") (pinfunction "PA12_33") (pintype "bidirectional"))
    )
    (net (code "23") (name "LED2") (class "Default")
      (node (ref "R3") (pin "2") (pinfunction "2_2") (pintype "passive"))
      (node (ref "U1") (pin "29") (pinfunction "PA8_29") (pintype "bidirectional"))
    )
    (net (code "24") (name "LED3") (class "Default")
      (node (ref "R4") (pin "2") (pinfunction "2_2") (pintype "passive"))
      (node (ref "U1") (pin "32") (pinfunction "PA11_32") (pintype "bidirectional"))
    )
    (net (code "25") (name "MISO") (class "Default")
      (node (ref "U1") (pin "16") (pinfunction "PA6_16") (pintype "bidirectional"))
      (node (ref "U4") (pin "2") (pinfunction "MISO_2") (pintype "bidirectional"))
    )
    (net (code "26") (name "MOSI") (class "Default")
      (node (ref "U1") (pin "17") (pinfunction "PA7_17") (pintype "bidirectional"))
      (node (ref "U4") (pin "3") (pinfunction "MOSI_3") (pintype "bidirectional"))
    )
    (net (code "27") (name "NSS") (class "Default")
      (node (ref "U1") (pin "38") (pinfunction "PA15_38") (pintype "bidirectional"))
      (node (ref "U4") (pin "5") (pinfunction "NSS_5") (pintype "bidirectional"))
    )
    (net (code "28") (name "Net-(CHRG-PadC)") (class "Default")
      (node (ref "CHRG") (pin "C") (pinfunction "C_C") (pintype "passive"))
      (node (ref "R9") (pin "2") (pinfunction "2_2") (pintype "passive"))
    )
    (net (code "29") (name "Net-(CON2-TP)") (class "Default")
      (node (ref "C21") (pin "2") (pinfunction "2_2") (pintype "passive"))
      (node (ref "CON2") (pin "1") (pinfunction "TP_1") (pintype "bidirectional"))
      (node (ref "CON3") (pin "1") (pinfunction "TP_1") (pintype "bidirectional"))
      (node (ref "R35") (pin "1") (pinfunction "1_1") (pintype "passive"))
    )
    (net (code "30") (name "Net-(FAULT-PadC)") (class "Default")
      (node (ref "FAULT") (pin "C") (pinfunction "C_C") (pintype "passive"))
      (node (ref "R10") (pin "2") (pinfunction "2_2") (pintype "passive"))
    )
    (net (code "31") (name "Net-(IPEX1-PadSIG)") (class "Default")
      (node (ref "IPEX1") (pin "SIG") (pinfunction "SIG_SIG") (pintype "passive"))
      (node (ref "R36") (pin "1") (pinfunction "1_1") (pintype "passive"))
    )
    (net (code "32") (name "Net-(K1-P$2-Pad3)") (class "Default")
      (node (ref "K1") (pin "3") (pinfunction "P$2_3") (pintype "bidirectional"))
      (node (ref "K1") (pin "4") (pinfunction "P$2_4") (pintype "bidirectional"))
      (node (ref "K1") (pin "6") (pinfunction "P$2_6") (pintype "bidirectional"))
      (node (ref "R2") (pin "2") (pinfunction "2_2") (pintype "passive"))
    )
    (net (code "33") (name "Net-(L1-Pad1)") (class "Default")
      (node (ref "L1") (pin "1") (pinfunction "1_1") (pintype "passive"))
      (node (ref "R34") (pin "2") (pinfunction "2_2") (pintype "passive"))
    )
    (net (code "34") (name "Net-(L3-P$2)") (class "Default")
      (node (ref "C11") (pin "+") (pinfunction "+_+") (pintype "passive"))
      (node (ref "C17") (pin "1") (pinfunction "1_1") (pintype "passive"))
      (node (ref "L3") (pin "2") (pinfunction "P$2_2") (pintype "bidirectional"))
      (node (ref "U3") (pin "8") (pinfunction "VCC_8") (pintype "bidirectional"))
    )
    (net (code "35") (name "Net-(Q3-1)") (class "Default")
      (node (ref "C2") (pin "2") (pinfunction "2_2") (pintype "passive"))
      (node (ref "Q3") (pin "3") (pinfunction "1_3") (pintype "passive"))
      (node (ref "U1") (pin "4") (pinfunction "PC15-OSC32_OUT_4") (pintype "bidirectional"))
    )
    (net (code "36") (name "Net-(Q3-2)") (class "Default")
      (node (ref "C1") (pin "2") (pinfunction "2_2") (pintype "passive"))
      (node (ref "Q3") (pin "4") (pinfunction "2_4") (pintype "passive"))
      (node (ref "U1") (pin "3") (pinfunction "PC14-OSC32_IN_3") (pintype "bidirectional"))
    )
    (net (code "37") (name "Net-(Q4-S)") (class "Default")
      (node (ref "Q4") (pin "2") (pinfunction "S_2") (pintype "passive"))
      (node (ref "R19") (pin "2") (pinfunction "2_2") (pintype "passive"))
    )
    (net (code "38") (name "Net-(Q11-G)") (class "Default")
      (node (ref "Q11") (pin "3") (pinfunction "G_3") (pintype "passive"))
      (node (ref "Q13") (pin "1") (pinfunction "D_1") (pintype "passive"))
      (node (ref "R16") (pin "2") (pinfunction "2_2") (pintype "passive"))
    )
    (net (code "39") (name "Net-(R20-Pad2)") (class "Default")
      (node (ref "R20") (pin "2") (pinfunction "2_2") (pintype "passive"))
      (node (ref "U3") (pin "18") (pinfunction "RESERVED_18") (pintype "bidirectional"))
    )
    (net (code "40") (name "Net-(R21-Pad2)") (class "Default")
      (node (ref "R21") (pin "2") (pinfunction "2_2") (pintype "passive"))
      (node (ref "U3") (pin "17") (pinfunction "RESERVED_17") (pintype "bidirectional"))
    )
    (net (code "41") (name "Net-(R22-Pad2)") (class "Default")
      (node (ref "R22") (pin "2") (pinfunction "2_2") (pintype "passive"))
      (node (ref "U3") (pin "16") (pinfunction "RESERVED_16") (pintype "bidirectional"))
    )
    (net (code "42") (name "Net-(STATUS-1)") (class "Default")
      (node (ref "R15") (pin "1") (pinfunction "1_1") (pintype "passive"))
      (node (ref "STATUS") (pin "R-") (pinfunction "1_R-") (pintype "passive"))
    )
    (net (code "43") (name "Net-(STATUS-3)") (class "Default")
      (node (ref "R3") (pin "1") (pinfunction "1_1") (pintype "passive"))
      (node (ref "STATUS") (pin "B-") (pinfunction "3_B-") (pintype "passive"))
    )
    (net (code "44") (name "Net-(STATUS-4)") (class "Default")
      (node (ref "R4") (pin "1") (pinfunction "1_1") (pintype "passive"))
      (node (ref "STATUS") (pin "G-") (pinfunction "4_G-") (pintype "passive"))
    )
    (net (code "45") (name "Net-(U2-ADO)") (class "Default")
      (node (ref "R26") (pin "2") (pinfunction "2_2") (pintype "passive"))
      (node (ref "U2") (pin "9") (pinfunction "ADO_9") (pintype "bidirectional"))
    )
    (net (code "46") (name "Net-(U2-FSYNC)") (class "Default")
      (node (ref "R28") (pin "2") (pinfunction "2_2") (pintype "passive"))
      (node (ref "U2") (pin "11") (pinfunction "FSYNC_11") (pintype "bidirectional"))
    )
    (net (code "47") (name "Net-(U2-INT)") (class "Default")
      (node (ref "R27") (pin "2") (pinfunction "2_2") (pintype "passive"))
      (node (ref "U2") (pin "12") (pinfunction "INT_12") (pintype "bidirectional"))
    )
    (net (code "48") (name "Net-(U2-NCS)") (class "Default")
      (node (ref "R31") (pin "2") (pinfunction "2_2") (pintype "passive"))
      (node (ref "U2") (pin "22") (pinfunction "NCS_22") (pintype "bidirectional"))
    )
    (net (code "49") (name "Net-(U2-REGOUT)") (class "Default")
      (node (ref "C6") (pin "2") (pinfunction "2_2") (pintype "passive"))
      (node (ref "U2") (pin "10") (pinfunction "REGOUT_10") (pintype "bidirectional"))
    )
    (net (code "50") (name "Net-(U5-BAT)") (class "Default")
      (node (ref "C15") (pin "1") (pinfunction "1_1") (pintype "passive"))
      (node (ref "R1") (pin "1") (pinfunction "1_1") (pintype "passive"))
      (node (ref "U5") (pin "5") (pinfunction "BAT_5") (pintype "bidirectional"))
    )
    (net (code "51") (name "Net-(U5-ISET)") (class "Default")
      (node (ref "R11") (pin "2") (pinfunction "2_2") (pintype "passive"))
      (node (ref "U5") (pin "2") (pinfunction "ISET_2") (pintype "bidirectional"))
    )
    (net (code "52") (name "Net-(U5-TEMP)") (class "Default")
      (node (ref "R12") (pin "1") (pinfunction "1_1") (pintype "passive"))
      (node (ref "R13") (pin "2") (pinfunction "2_2") (pintype "passive"))
      (node (ref "R17") (pin "1") (pinfunction "1_1") (pintype "passive"))
      (node (ref "U5") (pin "1") (pinfunction "TEMP_1") (pintype "bidirectional"))
    )
    (net (code "53") (name "Net-(U5-~{FAULT})") (class "Default")
      (node (ref "R10") (pin "1") (pinfunction "1_1") (pintype "passive"))
      (node (ref "U5") (pin "6") (pinfunction "~{FAULT}_6") (pintype "bidirectional"))
    )
    (net (code "54") (name "PA0") (class "Default")
      (node (ref "R23") (pin "1") (pinfunction "1_1") (pintype "passive"))
      (node (ref "R24") (pin "1") (pinfunction "1_1") (pintype "passive"))
      (node (ref "U1") (pin "10") (pinfunction "PA0-WKUP1_10") (pintype "bidirectional"))
    )
    (net (code "55") (name "PA1") (class "Default")
      (node (ref "R5") (pin "1") (pinfunction "1_1") (pintype "passive"))
      (node (ref "R6") (pin "1") (pinfunction "1_1") (pintype "passive"))
      (node (ref "U1") (pin "11") (pinfunction "PA1_11") (pintype "bidirectional"))
    )
    (net (code "56") (name "PA2") (class "Default")
      (node (ref "R23") (pin "2") (pinfunction "2_2") (pintype "passive"))
      (node (ref "U1") (pin "12") (pinfunction "PA2_12") (pintype "bidirectional"))
    )
    (net (code "57") (name "PA3") (class "Default")
      (node (ref "R37") (pin "1") (pinfunction "1_1") (pintype "passive"))
      (node (ref "R38") (pin "1") (pinfunction "1_1") (pintype "passive"))
      (node (ref "U1") (pin "13") (pinfunction "PA3_13") (pintype "bidirectional"))
    )
    (net (code "58") (name "PB5") (class "Default")
      (node (ref "Q13") (pin "3") (pinfunction "G_3") (pintype "passive"))
      (node (ref "R33") (pin "2") (pinfunction "2_2") (pintype "passive"))
      (node (ref "U1") (pin "41") (pinfunction "PB5_41") (pintype "bidirectional"))
    )
    (net (code "59") (name "PB13") (class "Default")
      (node (ref "U1") (pin "26") (pinfunction "PB13_26") (pintype "bidirectional"))
    )
    (net (code "60") (name "PB14") (class "Default")
      (node (ref "C7") (pin "2") (pinfunction "2_2") (pintype "passive"))
      (node (ref "R2") (pin "1") (pinfunction "1_1") (pintype "passive"))
      (node (ref "U1") (pin "27") (pinfunction "PB14_27") (pintype "bidirectional"))
    )
    (net (code "61") (name "PB15") (class "Default")
      (node (ref "U1") (pin "28") (pinfunction "PB15_28") (pintype "bidirectional"))
    )
    (net (code "62") (name "RESET") (class "Default")
      (node (ref "Q7") (pin "1") (pinfunction "D_1") (pintype "passive"))
      (node (ref "U3") (pin "9") (pinfunction "RESET_9") (pintype "bidirectional"))
    )
    (net (code "63") (name "RF_IN") (class "Default")
      (node (ref "C9") (pin "1") (pinfunction "1_1") (pintype "passive"))
      (node (ref "L1") (pin "2") (pinfunction "2_2") (pintype "passive"))
      (node (ref "R8") (pin "1") (pinfunction "1_1") (pintype "passive"))
      (node (ref "U3") (pin "11") (pinfunction "RF_IN_11") (pintype "bidirectional"))
    )
    (net (code "64") (name "RF_RESET") (class "Default")
      (node (ref "U1") (pin "18") (pinfunction "PB0_18") (pintype "bidirectional"))
      (node (ref "U4") (pin "6") (pinfunction "RESET_6") (pintype "bidirectional"))
    )
    (net (code "65") (name "RST") (class "Default")
      (node (ref "RST") (pin "P$1") (pinfunction "P$1_P$1") (pintype "bidirectional"))
      (node (ref "U1") (pin "7") (pinfunction "NRST_7") (pintype "bidirectional"))
    )
    (net (code "66") (name "RXD_MODULE") (class "Default")
      (node (ref "U1") (pin "42") (pinfunction "PB6_42") (pintype "bidirectional"))
      (node (ref "U3") (pin "3") (pinfunction "RXD_3") (pintype "bidirectional"))
    )
    (net (code "67") (name "SCK") (class "Default")
      (node (ref "U1") (pin "15") (pinfunction "PA5_15") (pintype "bidirectional"))
      (node (ref "U4") (pin "4") (pinfunction "SCK_4") (pintype "bidirectional"))
    )
    (net (code "68") (name "SCL") (class "Default")
      (node (ref "R14") (pin "1") (pinfunction "1_1") (pintype "passive"))
      (node (ref "U1") (pin "30") (pinfunction "PA9_30") (pintype "bidirectional"))
      (node (ref "U2") (pin "23") (pinfunction "SCL_23") (pintype "bidirectional"))
    )
    (net (code "69") (name "SDA") (class "Default")
      (node (ref "R7") (pin "1") (pinfunction "1_1") (pintype "passive"))
      (node (ref "U1") (pin "31") (pinfunction "PA10_31") (pintype "bidirectional"))
      (node (ref "U2") (pin "24") (pinfunction "SDA_24") (pintype "bidirectional"))
    )
    (net (code "70") (name "STANDBY") (class "Default")
      (node (ref "Q12") (pin "1") (pinfunction "D_1") (pintype "passive"))
      (node (ref "U3") (pin "5") (pinfunction "STANDBY_5") (pintype "bidirectional"))
    )
    (net (code "71") (name "SWCLK") (class "Default")
      (node (ref "D2") (pin "P$2") (pinfunction "2_P$2") (pintype "passive"))
      (node (ref "J2") (pin "P3") (pinfunction "D+_P3") (pintype "bidirectional"))
      (node (ref "R29") (pin "2") (pinfunction "2_2") (pintype "passive"))
      (node (ref "U1") (pin "37") (pinfunction "PA14_37") (pintype "bidirectional"))
    )
    (net (code "72") (name "SWDIO") (class "Default")
      (node (ref "D3") (pin "P$2") (pinfunction "2_P$2") (pintype "passive"))
      (node (ref "J2") (pin "P2") (pinfunction "D-_P2") (pintype "bidirectional"))
      (node (ref "R30") (pin "1") (pinfunction "1_1") (pintype "passive"))
      (node (ref "U1") (pin "34") (pinfunction "PA13_34") (pintype "bidirectional"))
    )
    (net (code "73") (name "TXD_MODULE") (class "Default")
      (node (ref "U1") (pin "43") (pinfunction "PB7_43") (pintype "bidirectional"))
      (node (ref "U3") (pin "2") (pinfunction "TXD_2") (pintype "bidirectional"))
    )
    (net (code "74") (name "UGND") (class "Default")
      (node (ref "J2") (pin "P5") (pinfunction "GND_P5") (pintype "passive"))
      (node (ref "L4") (pin "2") (pinfunction "P$2_2") (pintype "bidirectional"))
    )
    (net (code "75") (name "USBID") (class "Default")
      (node (ref "J2") (pin "P4") (pinfunction "ID_P4") (pintype "bidirectional"))
    )
    (net (code "76") (name "USB_5V") (class "Default")
      (node (ref "C16") (pin "1") (pinfunction "1_1") (pintype "passive"))
      (node (ref "C19") (pin "+") (pinfunction "+_+") (pintype "passive"))
      (node (ref "C20") (pin "1") (pinfunction "1_1") (pintype "passive"))
      (node (ref "CHRG") (pin "A") (pinfunction "A_A") (pintype "passive"))
      (node (ref "DD2") (pin "A") (pinfunction "A_A") (pintype "passive"))
      (node (ref "F1") (pin "1") (pinfunction "1_1") (pintype "passive"))
      (node (ref "FAULT") (pin "A") (pinfunction "A_A") (pintype "passive"))
      (node (ref "Q4") (pin "3") (pinfunction "G_3") (pintype "passive"))
      (node (ref "R12") (pin "2") (pinfunction "2_2") (pintype "passive"))
      (node (ref "R18") (pin "2") (pinfunction "2_2") (pintype "passive"))
      (node (ref "R37") (pin "2") (pinfunction "2_2") (pintype "passive"))
      (node (ref "U5") (pin "4") (pinfunction "VIN_4") (pintype "bidirectional"))
      (node (ref "U5") (pin "8") (pinfunction "CE_8") (pintype "bidirectional"))
    )
    (net (code "77") (name "VCC3V3_2") (class "Default")
      (node (ref "C36") (pin "2") (pinfunction "2_2") (pintype "passive"))
      (node (ref "C37") (pin "2") (pinfunction "2_2") (pintype "passive"))
      (node (ref "C8") (pin "2") (pinfunction "2_2") (pintype "passive"))
      (node (ref "R14") (pin "2") (pinfunction "2_2") (pintype "passive"))
      (node (ref "R31") (pin "1") (pinfunction "1_1") (pintype "passive"))
      (node (ref "R32") (pin "2") (pinfunction "2_2") (pintype "passive"))
      (node (ref "R7") (pin "2") (pinfunction "2_2") (pintype "passive"))
      (node (ref "U2") (pin "1") (pinfunction "RESV_1") (pintype "bidirectional"))
      (node (ref "U2") (pin "13") (pinfunction "VDD_13") (pintype "bidirectional"))
      (node (ref "U2") (pin "8") (pinfunction "VDDIO_8") (pintype "bidirectional"))
    )
    (net (code "78") (name "VCC_RF") (class "Default")
      (node (ref "R34") (pin "1") (pinfunction "1_1") (pintype "passive"))
      (node (ref "U3") (pin "14") (pinfunction "VCC_RF_14") (pintype "bidirectional"))
    )
    (net (code "79") (name "XUSB") (class "Default")
      (node (ref "F1") (pin "2") (pinfunction "2_2") (pintype "passive"))
      (node (ref "J2") (pin "P1") (pinfunction "VBUS_P1") (pintype "power_in"))
    )
    (net (code "80") (name "unconnected-(K3-Pad2)") (class "Default")
      (node (ref "K3") (pin "2") (pinfunction "2_2") (pintype "passive"))
    )
    (net (code "81") (name "unconnected-(U1-PH1-OSC_OUT-Pad6)") (class "Default")
      (node (ref "U1") (pin "6") (pinfunction "PH1-OSC_OUT_6") (pintype "bidirectional"))
    )
    (net (code "82") (name "unconnected-(U1-PHO-OSC_IN-Pad5)") (class "Default")
      (node (ref "U1") (pin "5") (pinfunction "PHO-OSC_IN_5") (pintype "bidirectional"))
    )
    (net (code "83") (name "unconnected-(U2-AUX_CL-Pad7)") (class "Default")
      (node (ref "U2") (pin "7") (pinfunction "AUX_CL_7") (pintype "bidirectional"))
    )
    (net (code "84") (name "unconnected-(U2-AUX_DA-Pad21)") (class "Default")
      (node (ref "U2") (pin "21") (pinfunction "AUX_DA_21") (pintype "bidirectional"))
    )
    (net (code "85") (name "unconnected-(U2-NC-Pad2)") (class "Default")
      (node (ref "U2") (pin "2") (pinfunction "NC_2") (pintype "bidirectional"))
    )
    (net (code "86") (name "unconnected-(U2-NC-Pad3)") (class "Default")
      (node (ref "U2") (pin "3") (pinfunction "NC_3") (pintype "bidirectional"))
    )
    (net (code "87") (name "unconnected-(U2-NC-Pad4)") (class "Default")
      (node (ref "U2") (pin "4") (pinfunction "NC_4") (pintype "bidirectional"))
    )
    (net (code "88") (name "unconnected-(U2-NC-Pad5)") (class "Default")
      (node (ref "U2") (pin "5") (pinfunction "NC_5") (pintype "input"))
    )
    (net (code "89") (name "unconnected-(U2-NC-Pad6)") (class "Default")
      (node (ref "U2") (pin "6") (pinfunction "NC_6") (pintype "bidirectional"))
    )
    (net (code "90") (name "unconnected-(U2-NC-Pad14)") (class "Default")
      (node (ref "U2") (pin "14") (pinfunction "NC_14") (pintype "bidirectional"))
    )
    (net (code "91") (name "unconnected-(U2-NC-Pad15)") (class "Default")
      (node (ref "U2") (pin "15") (pinfunction "NC_15") (pintype "bidirectional"))
    )
    (net (code "92") (name "unconnected-(U2-NC-Pad16)") (class "Default")
      (node (ref "U2") (pin "16") (pinfunction "NC_16") (pintype "bidirectional"))
    )
    (net (code "93") (name "unconnected-(U2-NC-Pad17)") (class "Default")
      (node (ref "U2") (pin "17") (pinfunction "NC_17") (pintype "bidirectional"))
    )
    (net (code "94") (name "unconnected-(U2-RESV-Pad19)") (class "Default")
      (node (ref "U2") (pin "19") (pinfunction "RESV_19") (pintype "bidirectional"))
    )
    (net (code "95") (name "unconnected-(U3-NC-Pad7)") (class "Default")
      (node (ref "U3") (pin "7") (pinfunction "NC_7") (pintype "bidirectional"))
    )
    (net (code "96") (name "unconnected-(U3-NC-Pad15)") (class "Default")
      (node (ref "U3") (pin "15") (pinfunction "NC_15") (pintype "bidirectional"))
    )
    (net (code "97") (name "unconnected-(U7-1-PadP$1)") (class "Default")
      (node (ref "U7") (pin "P$1") (pinfunction "1_P$1") (pintype "bidirectional"))
    )
    (net (code "98") (name "unconnected-(U7-2-PadP$2)") (class "Default")
      (node (ref "U7") (pin "P$2") (pinfunction "2_P$2") (pintype "bidirectional"))
    )
  )
)
